# uController.net
KiCad netlist of a schematic drawn in Altium Designer
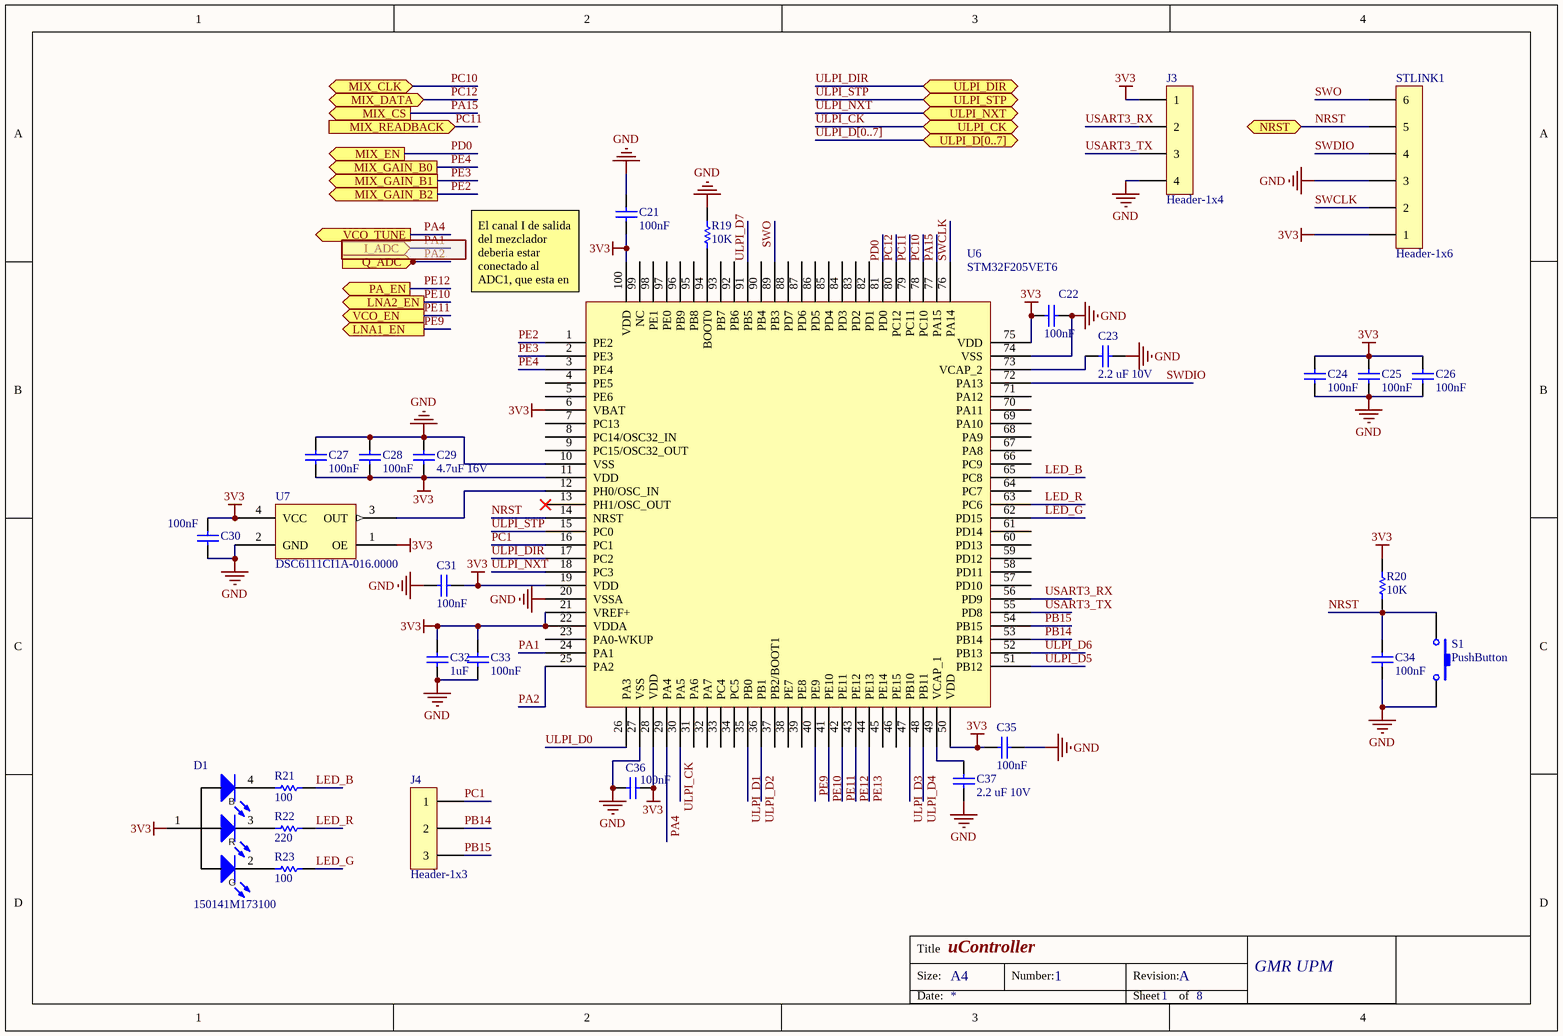
[diagram p0: uController.SchDoc]

(export (version "E")
  (design (tool "Eeschema 10.0.6"))
  (components
    (comp (ref "C21")
      (value "100nF")
      (footprint "0603 Cap")
      (description "CAP CER 0.1UF 16V X7R 0603")
      (fields
        (field (name "MANUFACTURER") "KEMET")
        (field (name "MANUFACTURER PART NUMBER") "C0603C104K4RACTU")
      )
      (libsource (lib "Componentes_base") (part "C0603C104K4RACTU"))
    )
    (comp (ref "C22")
      (value "100nF")
      (footprint "0603 Cap")
      (description "CAP CER 0.1UF 16V X7R 0603")
      (fields
        (field (name "MANUFACTURER") "KEMET")
        (field (name "MANUFACTURER PART NUMBER") "C0603C104K4RACTU")
      )
      (libsource (lib "Componentes_base") (part "C0603C104K4RACTU"))
    )
    (comp (ref "C23")
      (value "2.2 uF 10V")
      (footprint "0603 Cap")
      (description "CAP CER 2.2UF 10V X7R 0603")
      (fields
        (field (name "MANUFACTURER") "Samsung Electro-Mechanics America, Inc.")
        (field (name "MANUFACTURER PART NUMBER") "CL10B225KP8NNNC")
      )
      (libsource (lib "Componentes_base") (part "CL10B225KP8NNNC"))
    )
    (comp (ref "C24")
      (value "100nF")
      (footprint "0603 Cap")
      (description "CAP CER 0.1UF 16V X7R 0603")
      (fields
        (field (name "MANUFACTURER") "KEMET")
        (field (name "MANUFACTURER PART NUMBER") "C0603C104K4RACTU")
      )
      (libsource (lib "Componentes_base") (part "C0603C104K4RACTU"))
    )
    (comp (ref "C25")
      (value "100nF")
      (footprint "0603 Cap")
      (description "CAP CER 0.1UF 16V X7R 0603")
      (fields
        (field (name "MANUFACTURER") "KEMET")
        (field (name "MANUFACTURER PART NUMBER") "C0603C104K4RACTU")
      )
      (libsource (lib "Componentes_base") (part "C0603C104K4RACTU"))
    )
    (comp (ref "C26")
      (value "100nF")
      (footprint "0603 Cap")
      (description "CAP CER 0.1UF 16V X7R 0603")
      (fields
        (field (name "MANUFACTURER") "KEMET")
        (field (name "MANUFACTURER PART NUMBER") "C0603C104K4RACTU")
      )
      (libsource (lib "Componentes_base") (part "C0603C104K4RACTU"))
    )
    (comp (ref "C27")
      (value "100nF")
      (footprint "0603 Cap")
      (description "CAP CER 0.1UF 16V X7R 0603")
      (fields
        (field (name "MANUFACTURER") "KEMET")
        (field (name "MANUFACTURER PART NUMBER") "C0603C104K4RACTU")
      )
      (libsource (lib "Componentes_base") (part "C0603C104K4RACTU"))
    )
    (comp (ref "C28")
      (value "100nF")
      (footprint "0603 Cap")
      (description "CAP CER 0.1UF 16V X7R 0603")
      (fields
        (field (name "MANUFACTURER") "KEMET")
        (field (name "MANUFACTURER PART NUMBER") "C0603C104K4RACTU")
      )
      (libsource (lib "Componentes_base") (part "C0603C104K4RACTU"))
    )
    (comp (ref "C29")
      (value "4.7uF 16V")
      (footprint "0805 CAP")
      (description "CAP CER 4.7UF 16V X7R 0805")
      (fields
        (field (name "MANUFACTURER") "Murata Electronics North America")
        (field (name "MANUFACTURER PART NUMBER") "GRM21BR71C475KE51L")
      )
      (libsource (lib "Componentes_base") (part "GRM21BR71C475KE51L"))
    )
    (comp (ref "C30")
      (value "100nF")
      (footprint "0603 Cap")
      (description "CAP CER 0.1UF 16V X7R 0603")
      (fields
        (field (name "MANUFACTURER") "KEMET")
        (field (name "MANUFACTURER PART NUMBER") "C0603C104K4RACTU")
      )
      (libsource (lib "Componentes_base") (part "C0603C104K4RACTU"))
    )
    (comp (ref "C31")
      (value "100nF")
      (footprint "0603 Cap")
      (description "CAP CER 0.1UF 16V X7R 0603")
      (fields
        (field (name "MANUFACTURER") "KEMET")
        (field (name "MANUFACTURER PART NUMBER") "C0603C104K4RACTU")
      )
      (libsource (lib "Componentes_base") (part "C0603C104K4RACTU"))
    )
    (comp (ref "C32")
      (value "1uF")
      (footprint "0603 Cap")
      (description "CAP CER 1UF 16V X7R 0603")
      (fields
        (field (name "MANUFACTURER") "Samsung Electro-Mechanics America, Inc.")
        (field (name "MANUFACTURER PART NUMBER") "CL10B105MO8NNWC")
      )
      (libsource (lib "Componentes_base") (part "CL10B105MO8NNWC"))
    )
    (comp (ref "C33")
      (value "100nF")
      (footprint "0603 Cap")
      (description "CAP CER 0.1UF 16V X7R 0603")
      (fields
        (field (name "MANUFACTURER") "KEMET")
        (field (name "MANUFACTURER PART NUMBER") "C0603C104K4RACTU")
      )
      (libsource (lib "Componentes_base") (part "C0603C104K4RACTU"))
    )
    (comp (ref "C34")
      (value "100nF")
      (footprint "0603 Cap")
      (description "CAP CER 0.1UF 16V X7R 0603")
      (fields
        (field (name "MANUFACTURER") "KEMET")
        (field (name "MANUFACTURER PART NUMBER") "C0603C104K4RACTU")
      )
      (libsource (lib "Componentes_base") (part "C0603C104K4RACTU"))
    )
    (comp (ref "C35")
      (value "100nF")
      (footprint "0603 Cap")
      (description "CAP CER 0.1UF 16V X7R 0603")
      (fields
        (field (name "MANUFACTURER") "KEMET")
        (field (name "MANUFACTURER PART NUMBER") "C0603C104K4RACTU")
      )
      (libsource (lib "Componentes_base") (part "C0603C104K4RACTU"))
    )
    (comp (ref "C36")
      (value "100nF")
      (footprint "0603 Cap")
      (description "CAP CER 0.1UF 16V X7R 0603")
      (fields
        (field (name "MANUFACTURER") "KEMET")
        (field (name "MANUFACTURER PART NUMBER") "C0603C104K4RACTU")
      )
      (libsource (lib "Componentes_base") (part "C0603C104K4RACTU"))
    )
    (comp (ref "C37")
      (value "2.2 uF 10V")
      (footprint "0603 Cap")
      (description "CAP CER 2.2UF 10V X7R 0603")
      (fields
        (field (name "MANUFACTURER") "Samsung Electro-Mechanics America, Inc.")
        (field (name "MANUFACTURER PART NUMBER") "CL10B225KP8NNNC")
      )
      (libsource (lib "Componentes_base") (part "CL10B225KP8NNNC"))
    )
    (comp (ref "D1")
      (value "150141M173100")
      (footprint "DFN270P320X210-4N")
      (description "LED RGB CLEAR 1411 SMD")
      (fields (field (name "MANUFACTURER") "Wurth Electronics Inc."))
      (libsource (lib "Componentes_base") (part "150141M173100"))
    )
    (comp (ref "J3")
      (value "Header-1x4")
      (footprint "HEADER-1X4")
      (libsource (lib "B105connectors") (part "Header-1x4"))
    )
    (comp (ref "J4")
      (value "Header-1x3")
      (footprint "Header-1x3-Jumper")
      (libsource (lib "B105lib") (part "Header-1x3"))
    )
    (comp (ref "R19")
      (value "10K")
      (footprint "0603 Res")
      (description "RES SMD 10K OHM 1% 1/10W 0603")
      (fields
        (field (name "MANUFACTURER") "Yageo")
        (field (name "MANUFACTURER PART NUMBER") "RC0603FR-0710KL")
      )
      (libsource (lib "Componentes_base") (part "RC0603FR-0710KL"))
    )
    (comp (ref "R20")
      (value "10K")
      (footprint "0603 Res")
      (description "RES SMD 10K OHM 1% 1/10W 0603")
      (fields
        (field (name "MANUFACTURER") "Yageo")
        (field (name "MANUFACTURER PART NUMBER") "RC0603FR-0710KL")
      )
      (libsource (lib "Componentes_base") (part "RC0603FR-0710KL"))
    )
    (comp (ref "R21")
      (value "100")
      (footprint "RESC1005X04L")
      (description "RES 100 OHM 1/16W 1% 0402 SMD")
      (fields
        (field (name "MANUFACTURER") "Rohm Semiconductor")
        (field (name "MANUFACTURER PART NUMBER") "MCR01MRTF1000")
      )
      (libsource (lib "Componentes_base") (part "MCR01MRTF1000"))
    )
    (comp (ref "R22")
      (value "220")
      (footprint "RESC1005X04L")
      (description "RES SMD 220 OHM 1% 1/16W 0402")
      (fields
        (field (name "MANUFACTURER") "Yageo")
        (field (name "MANUFACTURER PART NUMBER") "RC0402FR-07220RL")
      )
      (libsource (lib "Componentes_base") (part "RC0402FR-07220RL"))
    )
    (comp (ref "R23")
      (value "100")
      (footprint "RESC1005X04L")
      (description "RES 100 OHM 1/16W 1% 0402 SMD")
      (fields
        (field (name "MANUFACTURER") "Rohm Semiconductor")
        (field (name "MANUFACTURER PART NUMBER") "MCR01MRTF1000")
      )
      (libsource (lib "Componentes_base") (part "MCR01MRTF1000"))
    )
    (comp (ref "S1")
      (value "PushButton")
      (footprint "GH7643CT-ND")
      (description "SWITCH TACTILE SPST-NO 0.05A 12V")
      (fields
        (field (name "MANUFACTURER") "Grayhill Inc.")
        (field (name "MANUFACTURER PART NUMBER") "95C04A3GWRT")
      )
      (libsource (lib "Schlib1") (part "PushButton_95C04A3GWRT"))
    )
    (comp (ref "STLINK1")
      (value "Header-1x6")
      (footprint "Header-1x6")
      (libsource (lib "B105connectors") (part "Header-1x6"))
    )
    (comp (ref "U6")
      (value "STM32F205VET6")
      (footprint "LQFP-100")
      (description "IC MCU 32BIT 512KB FLASH 100LQFP")
      (fields (field (name "MANUFACTURER") "STMicroelectronics"))
      (libsource (lib "Componentes_base") (part "STM32F205VET6"))
    )
    (comp (ref "U7")
      (value "DSC6111CI1A-016.0000")
      (footprint "DFN 3.2x2.5")
      (description "ULTRA-LOW POWER,MEMS OSCILLATOR,")
      (fields (field (name "MANUFACTURER") "Microchip Technology"))
      (libsource (lib "Componentes_base") (part "DSC6111CI1A-016.0000"))
    )
  )
  (nets
    (net (code "1") (name "/LED_B") (class "Default")
      (node (ref "R21") (pin "2") (pinfunction "2_2") (pintype "passive"))
      (node (ref "U6") (pin "65") (pinfunction "PC8_65") (pintype "passive"))
    )
    (net (code "2") (name "/LED_G") (class "Default")
      (node (ref "R23") (pin "2") (pinfunction "2_2") (pintype "passive"))
      (node (ref "U6") (pin "62") (pinfunction "PD15_62") (pintype "passive"))
    )
    (net (code "3") (name "/LED_R") (class "Default")
      (node (ref "R22") (pin "2") (pinfunction "2_2") (pintype "passive"))
      (node (ref "U6") (pin "63") (pinfunction "PC6_63") (pintype "passive"))
    )
    (net (code "4") (name "/NRST") (class "Default")
      (node (ref "C34") (pin "2") (pinfunction "2_2") (pintype "passive"))
      (node (ref "R20") (pin "1") (pinfunction "1_1") (pintype "passive"))
      (node (ref "S1") (pin "1") (pinfunction "1_1") (pintype "passive"))
      (node (ref "STLINK1") (pin "5") (pinfunction "5_5") (pintype "passive"))
      (node (ref "U6") (pin "14") (pinfunction "NRST_14") (pintype "passive"))
    )
    (net (code "5") (name "/PA1") (class "Default")
      (node (ref "U6") (pin "24") (pinfunction "PA1_24") (pintype "passive"))
    )
    (net (code "6") (name "/PA2") (class "Default")
      (node (ref "U6") (pin "25") (pinfunction "PA2_25") (pintype "passive"))
    )
    (net (code "7") (name "/PA4") (class "Default")
      (node (ref "U6") (pin "29") (pinfunction "PA4_29") (pintype "passive"))
    )
    (net (code "8") (name "/PA15") (class "Default")
      (node (ref "U6") (pin "77") (pinfunction "PA15_77") (pintype "passive"))
    )
    (net (code "9") (name "/PB14") (class "Default")
      (node (ref "J4") (pin "2") (pinfunction "2_2") (pintype "passive"))
      (node (ref "U6") (pin "53") (pinfunction "PB14_53") (pintype "passive"))
    )
    (net (code "10") (name "/PB15") (class "Default")
      (node (ref "J4") (pin "3") (pinfunction "3_3") (pintype "passive"))
      (node (ref "U6") (pin "54") (pinfunction "PB15_54") (pintype "passive"))
    )
    (net (code "11") (name "/PC1") (class "Default")
      (node (ref "J4") (pin "1") (pinfunction "1_1") (pintype "passive"))
      (node (ref "U6") (pin "16") (pinfunction "PC1_16") (pintype "passive"))
    )
    (net (code "12") (name "/PC10") (class "Default")
      (node (ref "U6") (pin "78") (pinfunction "PC10_78") (pintype "passive"))
    )
    (net (code "13") (name "/PC11") (class "Default")
      (node (ref "U6") (pin "79") (pinfunction "PC11_79") (pintype "passive"))
    )
    (net (code "14") (name "/PC12") (class "Default")
      (node (ref "U6") (pin "80") (pinfunction "PC12_80") (pintype "passive"))
    )
    (net (code "15") (name "/PD0") (class "Default")
      (node (ref "U6") (pin "81") (pinfunction "PD0_81") (pintype "passive"))
    )
    (net (code "16") (name "/PE2") (class "Default")
      (node (ref "U6") (pin "1") (pinfunction "PE2_1") (pintype "passive"))
    )
    (net (code "17") (name "/PE3") (class "Default")
      (node (ref "U6") (pin "2") (pinfunction "PE3_2") (pintype "passive"))
    )
    (net (code "18") (name "/PE4") (class "Default")
      (node (ref "U6") (pin "3") (pinfunction "PE4_3") (pintype "passive"))
    )
    (net (code "19") (name "/PE9") (class "Default")
      (node (ref "U6") (pin "40") (pinfunction "PE9_40") (pintype "passive"))
    )
    (net (code "20") (name "/PE10") (class "Default")
      (node (ref "U6") (pin "41") (pinfunction "PE10_41") (pintype "passive"))
    )
    (net (code "21") (name "/PE11") (class "Default")
      (node (ref "U6") (pin "42") (pinfunction "PE11_42") (pintype "passive"))
    )
    (net (code "22") (name "/PE12") (class "Default")
      (node (ref "U6") (pin "43") (pinfunction "PE12_43") (pintype "passive"))
    )
    (net (code "23") (name "/PE13") (class "Default")
      (node (ref "U6") (pin "44") (pinfunction "PE13_44") (pintype "passive"))
    )
    (net (code "24") (name "/SWCLK") (class "Default")
      (node (ref "STLINK1") (pin "2") (pinfunction "2_2") (pintype "passive"))
      (node (ref "U6") (pin "76") (pinfunction "PA14_76") (pintype "passive"))
    )
    (net (code "25") (name "/SWDIO") (class "Default")
      (node (ref "STLINK1") (pin "4") (pinfunction "4_4") (pintype "passive"))
      (node (ref "U6") (pin "72") (pinfunction "PA13_72") (pintype "passive"))
    )
    (net (code "26") (name "/SWO") (class "Default")
      (node (ref "STLINK1") (pin "6") (pinfunction "6_6") (pintype "passive"))
      (node (ref "U6") (pin "89") (pinfunction "PB3_89") (pintype "passive"))
    )
    (net (code "27") (name "/ULPI_CK") (class "Default")
      (node (ref "U6") (pin "30") (pinfunction "PA5_30") (pintype "passive"))
    )
    (net (code "28") (name "/ULPI_D0") (class "Default")
      (node (ref "U6") (pin "26") (pinfunction "PA3_26") (pintype "passive"))
    )
    (net (code "29") (name "/ULPI_D1") (class "Default")
      (node (ref "U6") (pin "35") (pinfunction "PB0_35") (pintype "passive"))
    )
    (net (code "30") (name "/ULPI_D2") (class "Default")
      (node (ref "U6") (pin "36") (pinfunction "PB1_36") (pintype "passive"))
    )
    (net (code "31") (name "/ULPI_D3") (class "Default")
      (node (ref "U6") (pin "47") (pinfunction "PB10_47") (pintype "passive"))
    )
    (net (code "32") (name "/ULPI_D4") (class "Default")
      (node (ref "U6") (pin "48") (pinfunction "PB11_48") (pintype "passive"))
    )
    (net (code "33") (name "/ULPI_D5") (class "Default")
      (node (ref "U6") (pin "51") (pinfunction "PB12_51") (pintype "passive"))
    )
    (net (code "34") (name "/ULPI_D6") (class "Default")
      (node (ref "U6") (pin "52") (pinfunction "PB13_52") (pintype "passive"))
    )
    (net (code "35") (name "/ULPI_D7") (class "Default")
      (node (ref "U6") (pin "91") (pinfunction "PB5_91") (pintype "passive"))
    )
    (net (code "36") (name "/ULPI_DIR") (class "Default")
      (node (ref "U6") (pin "17") (pinfunction "PC2_17") (pintype "passive"))
    )
    (net (code "38") (name "/ULPI_NXT") (class "Default")
      (node (ref "U6") (pin "18") (pinfunction "PC3_18") (pintype "passive"))
    )
    (net (code "39") (name "/ULPI_STP") (class "Default")
      (node (ref "U6") (pin "15") (pinfunction "PC0_15") (pintype "passive"))
    )
    (net (code "40") (name "/USART3_RX") (class "Default")
      (node (ref "J3") (pin "2") (pinfunction "2_2") (pintype "passive"))
      (node (ref "U6") (pin "56") (pinfunction "PD9_56") (pintype "passive"))
    )
    (net (code "41") (name "/USART3_TX") (class "Default")
      (node (ref "J3") (pin "3") (pinfunction "3_3") (pintype "passive"))
      (node (ref "U6") (pin "55") (pinfunction "PD8_55") (pintype "passive"))
    )
    (net (code "42") (name "3V3") (class "Default")
      (node (ref "C21") (pin "2") (pinfunction "2_2") (pintype "passive"))
      (node (ref "C22") (pin "1") (pinfunction "1_1") (pintype "passive"))
      (node (ref "C24") (pin "2") (pinfunction "2_2") (pintype "passive"))
      (node (ref "C25") (pin "2") (pinfunction "2_2") (pintype "passive"))
      (node (ref "C26") (pin "2") (pinfunction "2_2") (pintype "passive"))
      (node (ref "C27") (pin "1") (pinfunction "1_1") (pintype "passive"))
      (node (ref "C28") (pin "1") (pinfunction "1_1") (pintype "passive"))
      (node (ref "C29") (pin "1") (pinfunction "1_1") (pintype "passive"))
      (node (ref "C30") (pin "2") (pinfunction "2_2") (pintype "passive"))
      (node (ref "C31") (pin "1") (pinfunction "1_1") (pintype "passive"))
      (node (ref "C32") (pin "2") (pinfunction "2_2") (pintype "passive"))
      (node (ref "C33") (pin "1") (pinfunction "1_1") (pintype "passive"))
      (node (ref "C35") (pin "2") (pinfunction "2_2") (pintype "passive"))
      (node (ref "C36") (pin "1") (pinfunction "1_1") (pintype "passive"))
      (node (ref "D1") (pin "1") (pinfunction "A_1") (pintype "passive"))
      (node (ref "J3") (pin "1") (pinfunction "1_1") (pintype "passive"))
      (node (ref "R20") (pin "2") (pinfunction "2_2") (pintype "passive"))
      (node (ref "STLINK1") (pin "1") (pinfunction "1_1") (pintype "passive"))
      (node (ref "U6") (pin "100") (pinfunction "VDD_100") (pintype "passive"))
      (node (ref "U6") (pin "11") (pinfunction "VDD_11") (pintype "passive"))
      (node (ref "U6") (pin "19") (pinfunction "VDD_19") (pintype "passive"))
      (node (ref "U6") (pin "21") (pinfunction "VREF+_21") (pintype "passive"))
      (node (ref "U6") (pin "22") (pinfunction "VDDA_22") (pintype "passive"))
      (node (ref "U6") (pin "28") (pinfunction "VDD_28") (pintype "passive"))
      (node (ref "U6") (pin "50") (pinfunction "VDD_50") (pintype "passive"))
      (node (ref "U6") (pin "6") (pinfunction "VBAT_6") (pintype "passive"))
      (node (ref "U6") (pin "75") (pinfunction "VDD_75") (pintype "passive"))
      (node (ref "U7") (pin "1") (pinfunction "OE_1") (pintype "passive"))
      (node (ref "U7") (pin "4") (pinfunction "VCC_4") (pintype "power_in"))
    )
    (net (code "43") (name "GND") (class "Default")
      (node (ref "C21") (pin "1") (pinfunction "1_1") (pintype "passive"))
      (node (ref "C22") (pin "2") (pinfunction "2_2") (pintype "passive"))
      (node (ref "C23") (pin "1") (pinfunction "1_1") (pintype "passive"))
      (node (ref "C24") (pin "1") (pinfunction "1_1") (pintype "passive"))
      (node (ref "C25") (pin "1") (pinfunction "1_1") (pintype "passive"))
      (node (ref "C26") (pin "1") (pinfunction "1_1") (pintype "passive"))
      (node (ref "C27") (pin "2") (pinfunction "2_2") (pintype "passive"))
      (node (ref "C28") (pin "2") (pinfunction "2_2") (pintype "passive"))
      (node (ref "C29") (pin "2") (pinfunction "2_2") (pintype "passive"))
      (node (ref "C30") (pin "1") (pinfunction "1_1") (pintype "passive"))
      (node (ref "C31") (pin "2") (pinfunction "2_2") (pintype "passive"))
      (node (ref "C32") (pin "1") (pinfunction "1_1") (pintype "passive"))
      (node (ref "C33") (pin "2") (pinfunction "2_2") (pintype "passive"))
      (node (ref "C34") (pin "1") (pinfunction "1_1") (pintype "passive"))
      (node (ref "C35") (pin "1") (pinfunction "1_1") (pintype "passive"))
      (node (ref "C36") (pin "2") (pinfunction "2_2") (pintype "passive"))
      (node (ref "C37") (pin "1") (pinfunction "1_1") (pintype "passive"))
      (node (ref "J3") (pin "4") (pinfunction "4_4") (pintype "passive"))
      (node (ref "R19") (pin "2") (pinfunction "2_2") (pintype "passive"))
      (node (ref "S1") (pin "2") (pinfunction "2_2") (pintype "passive"))
      (node (ref "STLINK1") (pin "3") (pinfunction "3_3") (pintype "passive"))
      (node (ref "U6") (pin "10") (pinfunction "VSS_10") (pintype "passive"))
      (node (ref "U6") (pin "20") (pinfunction "VSSA_20") (pintype "passive"))
      (node (ref "U6") (pin "27") (pinfunction "VSS_27") (pintype "passive"))
      (node (ref "U6") (pin "74") (pinfunction "VSS_74") (pintype "passive"))
      (node (ref "U7") (pin "2") (pinfunction "GND_2") (pintype "power_in"))
    )
    (net (code "44") (name "Net-(D1-C-Pad2)") (class "Default")
      (node (ref "D1") (pin "2") (pinfunction "C_2") (pintype "passive"))
      (node (ref "R23") (pin "1") (pinfunction "1_1") (pintype "passive"))
    )
    (net (code "45") (name "Net-(D1-C-Pad3)") (class "Default")
      (node (ref "D1") (pin "3") (pinfunction "C_3") (pintype "passive"))
      (node (ref "R22") (pin "1") (pinfunction "1_1") (pintype "passive"))
    )
    (net (code "46") (name "Net-(D1-C-Pad4)") (class "Default")
      (node (ref "D1") (pin "4") (pinfunction "C_4") (pintype "passive"))
      (node (ref "R21") (pin "1") (pinfunction "1_1") (pintype "passive"))
    )
    (net (code "47") (name "Net-(U6-BOOT0)") (class "Default")
      (node (ref "R19") (pin "1") (pinfunction "1_1") (pintype "passive"))
      (node (ref "U6") (pin "94") (pinfunction "BOOT0_94") (pintype "passive"))
    )
    (net (code "48") (name "Net-(U6-PH0{slash}OSC_IN)") (class "Default")
      (node (ref "U6") (pin "12") (pinfunction "PH0/OSC_IN_12") (pintype "passive"))
      (node (ref "U7") (pin "3") (pinfunction "OUT_3") (pintype "output"))
    )
    (net (code "49") (name "Net-(U6-VCAP_1)") (class "Default")
      (node (ref "C37") (pin "2") (pinfunction "2_2") (pintype "passive"))
      (node (ref "U6") (pin "49") (pinfunction "VCAP_1_49") (pintype "passive"))
    )
    (net (code "50") (name "Net-(U6-VCAP_2)") (class "Default")
      (node (ref "C23") (pin "2") (pinfunction "2_2") (pintype "passive"))
      (node (ref "U6") (pin "73") (pinfunction "VCAP_2_73") (pintype "passive"))
    )
    (net (code "51") (name "unconnected-(U6-NC-Pad99)") (class "Default")
      (node (ref "U6") (pin "99") (pinfunction "NC_99") (pintype "passive"))
    )
    (net (code "52") (name "unconnected-(U6-PA0-WKUP-Pad23)") (class "Default")
      (node (ref "U6") (pin "23") (pinfunction "PA0-WKUP_23") (pintype "passive"))
    )
    (net (code "53") (name "unconnected-(U6-PA6-Pad31)") (class "Default")
      (node (ref "U6") (pin "31") (pinfunction "PA6_31") (pintype "passive"))
    )
    (net (code "54") (name "unconnected-(U6-PA7-Pad32)") (class "Default")
      (node (ref "U6") (pin "32") (pinfunction "PA7_32") (pintype "passive"))
    )
    (net (code "55") (name "unconnected-(U6-PA8-Pad67)") (class "Default")
      (node (ref "U6") (pin "67") (pinfunction "PA8_67") (pintype "passive"))
    )
    (net (code "56") (name "unconnected-(U6-PA9-Pad68)") (class "Default")
      (node (ref "U6") (pin "68") (pinfunction "PA9_68") (pintype "passive"))
    )
    (net (code "57") (name "unconnected-(U6-PA10-Pad69)") (class "Default")
      (node (ref "U6") (pin "69") (pinfunction "PA10_69") (pintype "passive"))
    )
    (net (code "58") (name "unconnected-(U6-PA11-Pad70)") (class "Default")
      (node (ref "U6") (pin "70") (pinfunction "PA11_70") (pintype "passive"))
    )
    (net (code "59") (name "unconnected-(U6-PA12-Pad71)") (class "Default")
      (node (ref "U6") (pin "71") (pinfunction "PA12_71") (pintype "passive"))
    )
    (net (code "60") (name "unconnected-(U6-PB2{slash}BOOT1-Pad37)") (class "Default")
      (node (ref "U6") (pin "37") (pinfunction "PB2/BOOT1_37") (pintype "passive"))
    )
    (net (code "61") (name "unconnected-(U6-PB4-Pad90)") (class "Default")
      (node (ref "U6") (pin "90") (pinfunction "PB4_90") (pintype "passive"))
    )
    (net (code "62") (name "unconnected-(U6-PB6-Pad92)") (class "Default")
      (node (ref "U6") (pin "92") (pinfunction "PB6_92") (pintype "passive"))
    )
    (net (code "63") (name "unconnected-(U6-PB7-Pad93)") (class "Default")
      (node (ref "U6") (pin "93") (pinfunction "PB7_93") (pintype "passive"))
    )
    (net (code "64") (name "unconnected-(U6-PB8-Pad95)") (class "Default")
      (node (ref "U6") (pin "95") (pinfunction "PB8_95") (pintype "passive"))
    )
    (net (code "65") (name "unconnected-(U6-PB9-Pad96)") (class "Default")
      (node (ref "U6") (pin "96") (pinfunction "PB9_96") (pintype "passive"))
    )
    (net (code "66") (name "unconnected-(U6-PC4-Pad33)") (class "Default")
      (node (ref "U6") (pin "33") (pinfunction "PC4_33") (pintype "passive"))
    )
    (net (code "67") (name "unconnected-(U6-PC5-Pad34)") (class "Default")
      (node (ref "U6") (pin "34") (pinfunction "PC5_34") (pintype "passive"))
    )
    (net (code "68") (name "unconnected-(U6-PC7-Pad64)") (class "Default")
      (node (ref "U6") (pin "64") (pinfunction "PC7_64") (pintype "passive"))
    )
    (net (code "69") (name "unconnected-(U6-PC9-Pad66)") (class "Default")
      (node (ref "U6") (pin "66") (pinfunction "PC9_66") (pintype "passive"))
    )
    (net (code "70") (name "unconnected-(U6-PC13-Pad7)") (class "Default")
      (node (ref "U6") (pin "7") (pinfunction "PC13_7") (pintype "passive"))
    )
    (net (code "71") (name "unconnected-(U6-PC14{slash}OSC32_IN-Pad8)") (class "Default")
      (node (ref "U6") (pin "8") (pinfunction "PC14/OSC32_IN_8") (pintype "passive"))
    )
    (net (code "72") (name "unconnected-(U6-PC15{slash}OSC32_OUT-Pad9)") (class "Default")
      (node (ref "U6") (pin "9") (pinfunction "PC15/OSC32_OUT_9") (pintype "passive"))
    )
    (net (code "73") (name "unconnected-(U6-PD1-Pad82)") (class "Default")
      (node (ref "U6") (pin "82") (pinfunction "PD1_82") (pintype "passive"))
    )
    (net (code "74") (name "unconnected-(U6-PD2-Pad83)") (class "Default")
      (node (ref "U6") (pin "83") (pinfunction "PD2_83") (pintype "passive"))
    )
    (net (code "75") (name "unconnected-(U6-PD3-Pad84)") (class "Default")
      (node (ref "U6") (pin "84") (pinfunction "PD3_84") (pintype "passive"))
    )
    (net (code "76") (name "unconnected-(U6-PD4-Pad85)") (class "Default")
      (node (ref "U6") (pin "85") (pinfunction "PD4_85") (pintype "passive"))
    )
    (net (code "77") (name "unconnected-(U6-PD5-Pad86)") (class "Default")
      (node (ref "U6") (pin "86") (pinfunction "PD5_86") (pintype "passive"))
    )
    (net (code "78") (name "unconnected-(U6-PD6-Pad87)") (class "Default")
      (node (ref "U6") (pin "87") (pinfunction "PD6_87") (pintype "passive"))
    )
    (net (code "79") (name "unconnected-(U6-PD7-Pad88)") (class "Default")
      (node (ref "U6") (pin "88") (pinfunction "PD7_88") (pintype "passive"))
    )
    (net (code "80") (name "unconnected-(U6-PD10-Pad57)") (class "Default")
      (node (ref "U6") (pin "57") (pinfunction "PD10_57") (pintype "passive"))
    )
    (net (code "81") (name "unconnected-(U6-PD11-Pad58)") (class "Default")
      (node (ref "U6") (pin "58") (pinfunction "PD11_58") (pintype "passive"))
    )
    (net (code "82") (name "unconnected-(U6-PD12-Pad59)") (class "Default")
      (node (ref "U6") (pin "59") (pinfunction "PD12_59") (pintype "passive"))
    )
    (net (code "83") (name "unconnected-(U6-PD13-Pad60)") (class "Default")
      (node (ref "U6") (pin "60") (pinfunction "PD13_60") (pintype "passive"))
    )
    (net (code "84") (name "unconnected-(U6-PD14-Pad61)") (class "Default")
      (node (ref "U6") (pin "61") (pinfunction "PD14_61") (pintype "passive"))
    )
    (net (code "85") (name "unconnected-(U6-PE0-Pad97)") (class "Default")
      (node (ref "U6") (pin "97") (pinfunction "PE0_97") (pintype "passive"))
    )
    (net (code "86") (name "unconnected-(U6-PE1-Pad98)") (class "Default")
      (node (ref "U6") (pin "98") (pinfunction "PE1_98") (pintype "passive"))
    )
    (net (code "87") (name "unconnected-(U6-PE5-Pad4)") (class "Default")
      (node (ref "U6") (pin "4") (pinfunction "PE5_4") (pintype "passive"))
    )
    (net (code "88") (name "unconnected-(U6-PE6-Pad5)") (class "Default")
      (node (ref "U6") (pin "5") (pinfunction "PE6_5") (pintype "passive"))
    )
    (net (code "89") (name "unconnected-(U6-PE7-Pad38)") (class "Default")
      (node (ref "U6") (pin "38") (pinfunction "PE7_38") (pintype "passive"))
    )
    (net (code "90") (name "unconnected-(U6-PE8-Pad39)") (class "Default")
      (node (ref "U6") (pin "39") (pinfunction "PE8_39") (pintype "passive"))
    )
    (net (code "91") (name "unconnected-(U6-PE14-Pad45)") (class "Default")
      (node (ref "U6") (pin "45") (pinfunction "PE14_45") (pintype "passive"))
    )
    (net (code "92") (name "unconnected-(U6-PE15-Pad46)") (class "Default")
      (node (ref "U6") (pin "46") (pinfunction "PE15_46") (pintype "passive"))
    )
    (net (code "93") (name "unconnected-(U6-PH1{slash}OSC_OUT-Pad13)") (class "Default")
      (node (ref "U6") (pin "13") (pinfunction "PH1/OSC_OUT_13") (pintype "passive+no_connect"))
    )
  )
)
